# Channel.net
KiCad netlist of a schematic drawn in Altium Designer
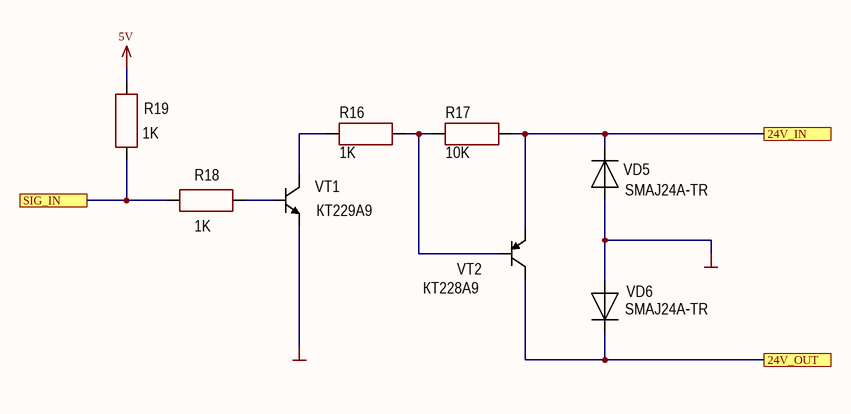
[diagram p0: Channel.SchDoc]

(export (version "E")
  (design (tool "Eeschema 10.0.6"))
  (components
    (comp (ref "R16")
      (value "1K")
      (footprint "RES: 1206")
      (fields
        (field (name "MANUFACTURER") "Yageo")
        (field (name "PARTNUMBER") "RC1206JR-07100RL")
        (field (name "VALUEMANUFACTURERPARTNUMBER") "Resistor film, 1K, ±5%, 1206, 0.25W, -55...+125°C")
      )
      (libsource (lib "Resistor") (part "Resistor_1206"))
    )
    (comp (ref "R17")
      (value "10K")
      (footprint "RES: 1206")
      (fields
        (field (name "MANUFACTURER") "Yageo")
        (field (name "PARTNUMBER") "RC1206JR-07100RL")
        (field (name "VALUEMANUFACTURERPARTNUMBER") "Resistor film, 10K, ±5%, 1206, 0.25W, -55...+125°C")
      )
      (libsource (lib "Resistor") (part "Resistor_1206"))
    )
    (comp (ref "R18")
      (value "1K")
      (footprint "RES: 0805")
      (fields
        (field (name "MANUFACTURER") "Yageo")
        (field (name "PARTNUMBER") "RC0805JR-07100RL")
        (field (name "VALUEMANUFACTURERPARTNUMBER") "Resistor film, 1K, ±5%, 0805, 0.125W, -55...+125°C")
      )
      (libsource (lib "Resistor") (part "Resistor_0805"))
    )
    (comp (ref "R19")
      (value "1K")
      (footprint "RES: 0805")
      (fields
        (field (name "MANUFACTURER") "Yageo")
        (field (name "PARTNUMBER") "RC0805JR-07100RL")
        (field (name "VALUEMANUFACTURERPARTNUMBER") "Resistor film, 1K, ±5%, 0805, 0.125W, -55...+125°C")
      )
      (libsource (lib "") (part "Resistor_0805_1"))
    )
    (comp (ref "VD5")
      (value "~")
      (footprint "DIODE: SMA")
      (fields
        (field (name "MANUFACTURER") "Micro Commercial")
        (field (name "VALUEMANUFACTURERPARTNUMBER") "Single diode, 75V, 150mA, 1V, 4ns, SOD-323, -55...+150°C")
        (field (name "VOLTAGE") "75V")
        (field (name "PARTNUMBER") "SMAJ24A-TR")
      )
      (libsource (lib "Diode") (part "Diode_single"))
    )
    (comp (ref "VD6")
      (value "~")
      (footprint "DIODE: SMA")
      (fields
        (field (name "MANUFACTURER") "Micro Commercial")
        (field (name "VALUEMANUFACTURERPARTNUMBER") "Single diode, 75V, 150mA, 1V, 4ns, SOD-323, -55...+150°C")
        (field (name "VOLTAGE") "75V")
        (field (name "PARTNUMBER") "SMAJ24A-TR")
      )
      (libsource (lib "Diode") (part "Diode_single"))
    )
    (comp (ref "VT1")
      (value "~")
      (footprint "SOT23")
      (fields
        (field (name "MANUFACTURER") "ON Semiconductor")
        (field (name "VALUEMANUFACTURERPARTNUMBER") "NPN transistor, 45V, 100mA, 100MHz, 300mW, 0.6V, 420, SOT-23, -55...+125°C")
        (field (name "PARTNUMBER") "КТ229А9")
      )
      (libsource (lib "Transistor") (part "BJT_NPN_132"))
    )
    (comp (ref "VT2")
      (value "~")
      (footprint "SOT23")
      (fields
        (field (name "MANUFACTURER") "ON Semiconductor")
        (field (name "VALUEMANUFACTURERPARTNUMBER") "PNP transistor, 45V, 100mA, 100MHz, 300mW, 0.65V, 220, SOT-23, -55...+125°C")
        (field (name "PARTNUMBER") "КТ228А9")
      )
      (libsource (lib "Transistor") (part "BJT_PNP_123"))
    )
  )
  (nets
    (net (code "1") (name "/24V_IN") (class "Default")
      (node (ref "R17") (pin "1") (pinfunction "1_1") (pintype "passive"))
      (node (ref "VD5") (pin "2") (pinfunction "2_2") (pintype "passive"))
      (node (ref "VT2") (pin "2") (pinfunction "E_2") (pintype "passive"))
    )
    (net (code "2") (name "/24V_OUT") (class "Default")
      (node (ref "VD6") (pin "2") (pinfunction "2_2") (pintype "passive"))
      (node (ref "VT2") (pin "3") (pinfunction "C_3") (pintype "passive"))
    )
    (net (code "3") (name "/SIG_IN") (class "Default")
      (node (ref "R18") (pin "1") (pinfunction "1_1") (pintype "passive"))
      (node (ref "R19") (pin "1") (pinfunction "1_1") (pintype "passive"))
    )
    (net (code "4") (name "5V") (class "Default")
      (node (ref "R19") (pin "2") (pinfunction "2_2") (pintype "passive"))
    )
    (net (code "5") (name "GND") (class "Default")
      (node (ref "VD5") (pin "1") (pinfunction "1_1") (pintype "passive"))
      (node (ref "VD6") (pin "1") (pinfunction "1_1") (pintype "passive"))
      (node (ref "VT1") (pin "2") (pinfunction "E_2") (pintype "passive"))
    )
    (net (code "6") (name "Net-(VT1-B)") (class "Default")
      (node (ref "R18") (pin "2") (pinfunction "2_2") (pintype "passive"))
      (node (ref "VT1") (pin "1") (pinfunction "B_1") (pintype "passive"))
    )
    (net (code "7") (name "Net-(VT1-C)") (class "Default")
      (node (ref "R16") (pin "2") (pinfunction "2_2") (pintype "passive"))
      (node (ref "VT1") (pin "3") (pinfunction "C_3") (pintype "passive"))
    )
    (net (code "8") (name "Net-(VT2-B)") (class "Default")
      (node (ref "R16") (pin "1") (pinfunction "1_1") (pintype "passive"))
      (node (ref "R17") (pin "2") (pinfunction "2_2") (pintype "passive"))
      (node (ref "VT2") (pin "1") (pinfunction "B_1") (pintype "passive"))
    )
  )
)
